# nixie-clock.net
KiCad netlist of a schematic drawn in EAGLE
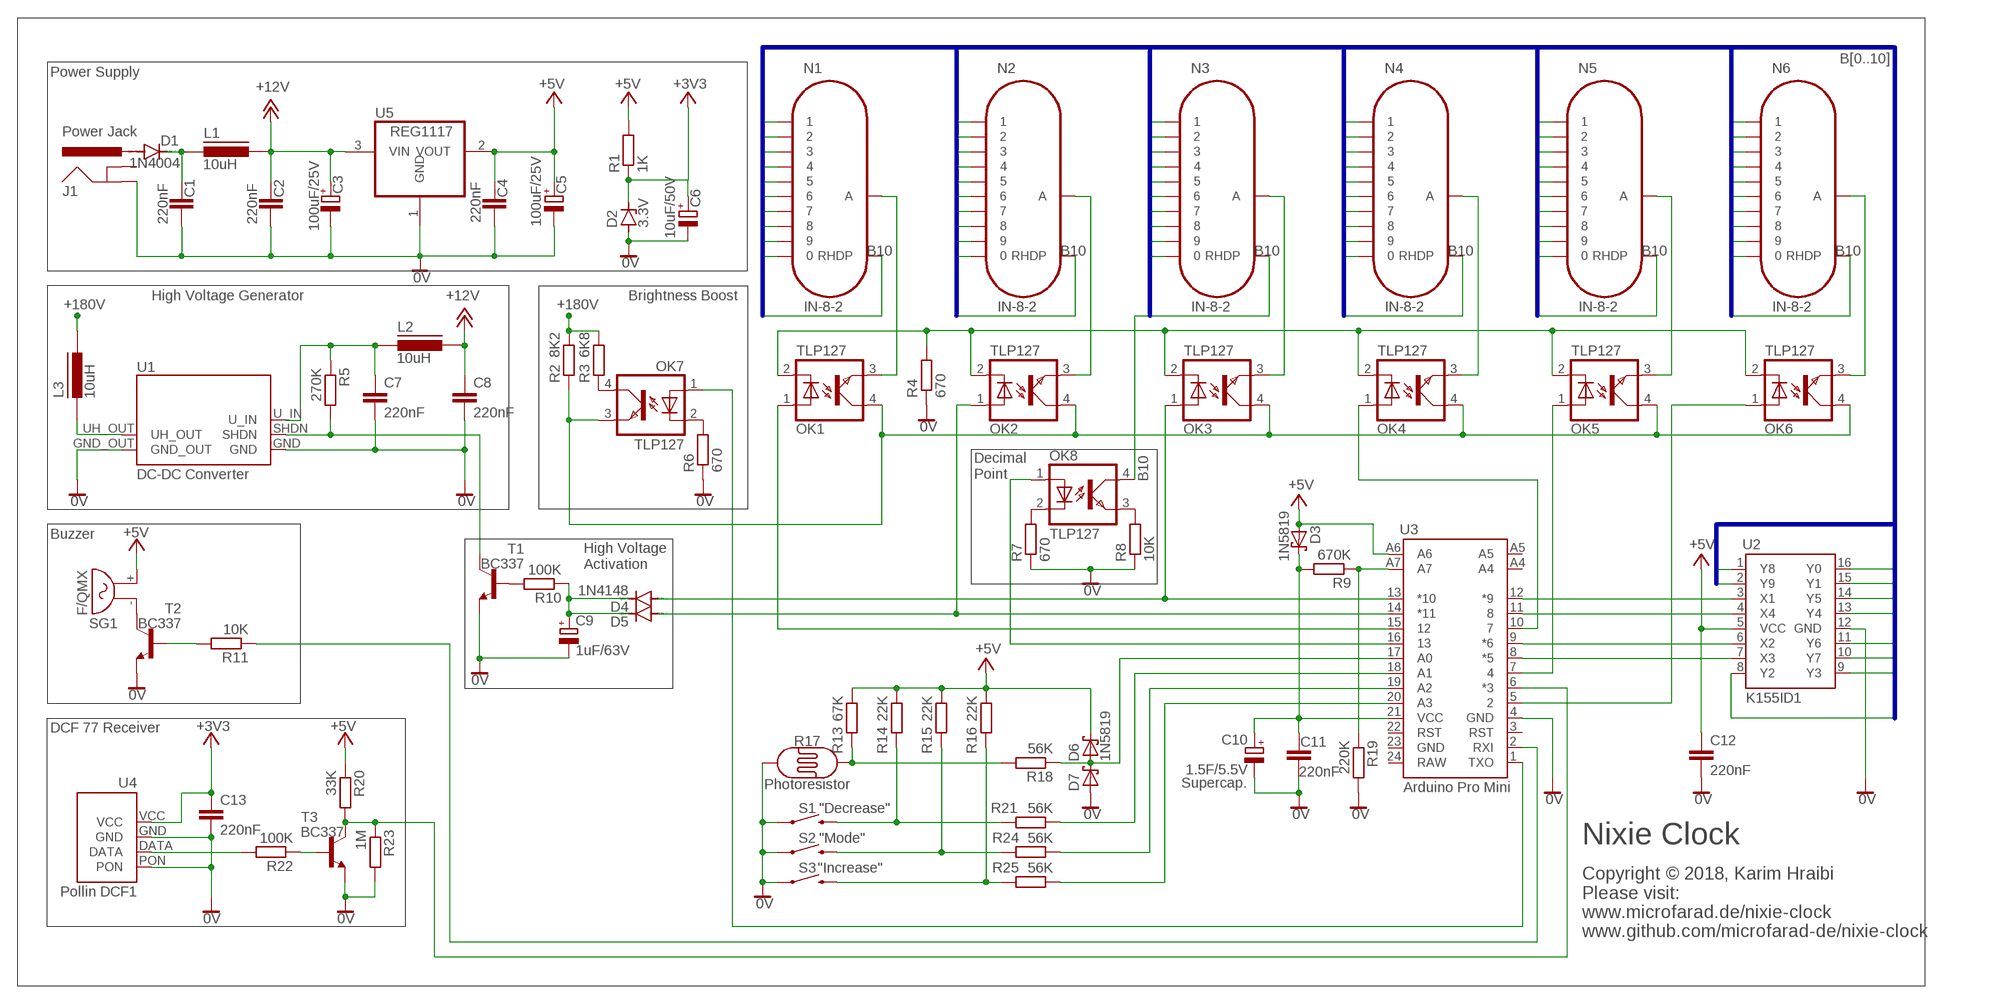
[diagram p0: schematic, sheet 1]

(export (version "E")
  (design (tool "Eeschema 10.0.6"))
  (components
    (comp (ref "C1")
      (value "220nF")
      (footprint "eagle-import:C025-024X044")
      (libsource (lib "eagle-import") (part "C-EU025-024X044"))
    )
    (comp (ref "C2")
      (value "220nF")
      (footprint "eagle-import:C025-024X044")
      (libsource (lib "eagle-import") (part "C-EU025-024X044"))
    )
    (comp (ref "C3")
      (value "100uF/25V")
      (footprint "eagle-import:E2,5-6")
      (libsource (lib "eagle-import") (part "CPOL-EUE2.5-6"))
    )
    (comp (ref "C4")
      (value "220nF")
      (footprint "eagle-import:C025-024X044")
      (libsource (lib "eagle-import") (part "C-EU025-024X044"))
    )
    (comp (ref "C5")
      (value "100uF/25V")
      (footprint "eagle-import:E2,5-6")
      (libsource (lib "eagle-import") (part "CPOL-EUE2.5-6"))
    )
    (comp (ref "C6")
      (value "10uF/50V")
      (footprint "eagle-import:E2-4")
      (libsource (lib "eagle-import") (part "CPOL-EUE2-4"))
    )
    (comp (ref "C7")
      (value "220nF")
      (footprint "eagle-import:C025-024X044")
      (libsource (lib "eagle-import") (part "C-EU025-024X044"))
    )
    (comp (ref "C8")
      (value "220nF")
      (footprint "eagle-import:C025-024X044")
      (libsource (lib "eagle-import") (part "C-EU025-024X044"))
    )
    (comp (ref "C9")
      (value "1uF/63V")
      (footprint "eagle-import:E1,8-4")
      (libsource (lib "eagle-import") (part "CPOL-EUE1.8-4"))
    )
    (comp (ref "C10")
      (value "1.5F/5.5V")
      (footprint "eagle-import:SUPERCAP_1.5F_5.5V")
      (libsource (lib "eagle-import") (part "SUPERCAP/1.5F/5.5V"))
    )
    (comp (ref "C11")
      (value "220nF")
      (footprint "eagle-import:C025-024X044")
      (libsource (lib "eagle-import") (part "C-EU025-024X044"))
    )
    (comp (ref "C12")
      (value "220nF")
      (footprint "eagle-import:C025-024X044")
      (libsource (lib "eagle-import") (part "C-EU025-024X044"))
    )
    (comp (ref "C13")
      (value "220nF")
      (footprint "eagle-import:C025-024X044")
      (libsource (lib "eagle-import") (part "C-EU025-024X044"))
    )
    (comp (ref "D1")
      (value "1N4004")
      (footprint "eagle-import:DO41-10")
      (libsource (lib "eagle-import") (part "1N4004"))
    )
    (comp (ref "D2")
      (value "3.3V")
      (footprint "eagle-import:ZDIO-5")
      (libsource (lib "eagle-import") (part "ZENER-DIODEZD-5"))
    )
    (comp (ref "D3")
      (value "1N5819")
      (footprint "eagle-import:DO41-7.6")
      (libsource (lib "eagle-import") (part "1N5819-B"))
    )
    (comp (ref "D4")
      (value "1N4148")
      (footprint "eagle-import:DO35-7")
      (libsource (lib "eagle-import") (part "1N4148DO35-7"))
    )
    (comp (ref "D5")
      (value "1N4148")
      (footprint "eagle-import:DO35-7")
      (libsource (lib "eagle-import") (part "1N4148DO35-7"))
    )
    (comp (ref "D6")
      (value "1N5819")
      (footprint "eagle-import:DO41-7.6")
      (libsource (lib "eagle-import") (part "1N5819-B"))
    )
    (comp (ref "D7")
      (value "1N5819")
      (footprint "eagle-import:DO41-7.6")
      (libsource (lib "eagle-import") (part "1N5819-B"))
    )
    (comp (ref "J1")
      (value "Power Jack")
      (footprint "eagle-import:POWER_JACK_SLOT")
      (libsource (lib "eagle-import") (part "POWER_JACKSLT"))
    )
    (comp (ref "L1")
      (value "10uH")
      (footprint "eagle-import:CHOKE_9.5MM")
      (libsource (lib "eagle-import") (part "CHOKE/9.5MM"))
    )
    (comp (ref "L2")
      (value "10uH")
      (footprint "eagle-import:CHOKE_9.5MM")
      (libsource (lib "eagle-import") (part "CHOKE/9.5MM"))
    )
    (comp (ref "L3")
      (value "10uH")
      (footprint "eagle-import:CHOKE_9.5MM")
      (libsource (lib "eagle-import") (part "CHOKE/9.5MM"))
    )
    (comp (ref "N1")
      (value "IN-8-2")
      (footprint "eagle-import:IN-8-2")
      (libsource (lib "eagle-import") (part "IN-8-2"))
    )
    (comp (ref "N2")
      (value "IN-8-2")
      (footprint "eagle-import:IN-8-2")
      (libsource (lib "eagle-import") (part "IN-8-2"))
    )
    (comp (ref "N3")
      (value "IN-8-2")
      (footprint "eagle-import:IN-8-2")
      (libsource (lib "eagle-import") (part "IN-8-2"))
    )
    (comp (ref "N4")
      (value "IN-8-2")
      (footprint "eagle-import:IN-8-2")
      (libsource (lib "eagle-import") (part "IN-8-2"))
    )
    (comp (ref "N5")
      (value "IN-8-2")
      (footprint "eagle-import:IN-8-2")
      (libsource (lib "eagle-import") (part "IN-8-2"))
    )
    (comp (ref "N6")
      (value "IN-8-2")
      (footprint "eagle-import:IN-8-2")
      (libsource (lib "eagle-import") (part "IN-8-2"))
    )
    (comp (ref "OK1")
      (value "TLP127")
      (footprint "eagle-import:MINI-FLAT-4")
      (libsource (lib "eagle-import") (part "TLP127"))
    )
    (comp (ref "OK2")
      (value "TLP127")
      (footprint "eagle-import:MINI-FLAT-4")
      (libsource (lib "eagle-import") (part "TLP127"))
    )
    (comp (ref "OK3")
      (value "TLP127")
      (footprint "eagle-import:MINI-FLAT-4")
      (libsource (lib "eagle-import") (part "TLP127"))
    )
    (comp (ref "OK4")
      (value "TLP127")
      (footprint "eagle-import:MINI-FLAT-4")
      (libsource (lib "eagle-import") (part "TLP127"))
    )
    (comp (ref "OK5")
      (value "TLP127")
      (footprint "eagle-import:MINI-FLAT-4")
      (libsource (lib "eagle-import") (part "TLP127"))
    )
    (comp (ref "OK6")
      (value "TLP127")
      (footprint "eagle-import:MINI-FLAT-4")
      (libsource (lib "eagle-import") (part "TLP127"))
    )
    (comp (ref "OK7")
      (value "TLP127")
      (footprint "eagle-import:MINI-FLAT-4")
      (libsource (lib "eagle-import") (part "TLP127"))
    )
    (comp (ref "OK8")
      (value "TLP127")
      (footprint "eagle-import:MINI-FLAT-4")
      (libsource (lib "eagle-import") (part "TLP127"))
    )
    (comp (ref "R1")
      (value "1K")
      (footprint "eagle-import:0207_7")
      (libsource (lib "eagle-import") (part "R-EU_0207/7"))
    )
    (comp (ref "R2")
      (value "8K2")
      (footprint "eagle-import:0207_7")
      (libsource (lib "eagle-import") (part "R-EU_0207/7"))
    )
    (comp (ref "R3")
      (value "6K8")
      (footprint "eagle-import:0207_7")
      (libsource (lib "eagle-import") (part "R-EU_0207/7"))
    )
    (comp (ref "R4")
      (value "670")
      (footprint "eagle-import:0207_7")
      (libsource (lib "eagle-import") (part "R-EU_0207/7"))
    )
    (comp (ref "R5")
      (value "270K")
      (footprint "eagle-import:0207_7")
      (libsource (lib "eagle-import") (part "R-EU_0207/7"))
    )
    (comp (ref "R6")
      (value "670")
      (footprint "eagle-import:0207_7")
      (libsource (lib "eagle-import") (part "R-EU_0207/7"))
    )
    (comp (ref "R7")
      (value "670")
      (footprint "eagle-import:0207_7")
      (libsource (lib "eagle-import") (part "R-EU_0207/7"))
    )
    (comp (ref "R8")
      (value "10K")
      (footprint "eagle-import:0207_7")
      (libsource (lib "eagle-import") (part "R-EU_0207/7"))
    )
    (comp (ref "R9")
      (value "670K")
      (footprint "eagle-import:0207_7")
      (libsource (lib "eagle-import") (part "R-EU_0207/7"))
    )
    (comp (ref "R10")
      (value "100K")
      (footprint "eagle-import:0207_7")
      (libsource (lib "eagle-import") (part "R-EU_0207/7"))
    )
    (comp (ref "R11")
      (value "10K")
      (footprint "eagle-import:0207_7")
      (libsource (lib "eagle-import") (part "R-EU_0207/7"))
    )
    (comp (ref "R13")
      (value "67K")
      (footprint "eagle-import:0207_7")
      (libsource (lib "eagle-import") (part "R-EU_0207/7"))
    )
    (comp (ref "R14")
      (value "22K")
      (footprint "eagle-import:0207_7")
      (libsource (lib "eagle-import") (part "R-EU_0207/7"))
    )
    (comp (ref "R15")
      (value "22K")
      (footprint "eagle-import:0207_7")
      (libsource (lib "eagle-import") (part "R-EU_0207/7"))
    )
    (comp (ref "R16")
      (value "22K")
      (footprint "eagle-import:0207_7")
      (libsource (lib "eagle-import") (part "R-EU_0207/7"))
    )
    (comp (ref "R17")
      (value "Photoresistor")
      (footprint "eagle-import:PHOTOCELL")
      (libsource (lib "eagle-import") (part "PHOTOCELLPTH"))
    )
    (comp (ref "R18")
      (value "56K")
      (footprint "eagle-import:0207_7")
      (libsource (lib "eagle-import") (part "R-EU_0207/7"))
    )
    (comp (ref "R19")
      (value "220K")
      (footprint "eagle-import:0207_7")
      (libsource (lib "eagle-import") (part "R-EU_0207/7"))
    )
    (comp (ref "R20")
      (value "33K")
      (footprint "eagle-import:0207_7")
      (libsource (lib "eagle-import") (part "R-EU_0207/7"))
    )
    (comp (ref "R21")
      (value "56K")
      (footprint "eagle-import:0207_7")
      (libsource (lib "eagle-import") (part "R-EU_0207/7"))
    )
    (comp (ref "R22")
      (value "100K")
      (footprint "eagle-import:0207_7")
      (libsource (lib "eagle-import") (part "R-EU_0207/7"))
    )
    (comp (ref "R23")
      (value "1M")
      (footprint "eagle-import:0207_7")
      (libsource (lib "eagle-import") (part "R-EU_0207/7"))
    )
    (comp (ref "R24")
      (value "56K")
      (footprint "eagle-import:0207_7")
      (libsource (lib "eagle-import") (part "R-EU_0207/7"))
    )
    (comp (ref "R25")
      (value "56K")
      (footprint "eagle-import:0207_7")
      (libsource (lib "eagle-import") (part "R-EU_0207/7"))
    )
    (comp (ref "S1")
      (value "\"Decrease\"")
      (footprint "eagle-import:TACTILE_SWITCH_PTH_6.0MM")
      (libsource (lib "eagle-import") (part "MOMENTARY-SWITCH-SPST-PTH-6.0MM"))
    )
    (comp (ref "S2")
      (value "\"Mode\"")
      (footprint "eagle-import:TACTILE_SWITCH_PTH_6.0MM")
      (libsource (lib "eagle-import") (part "MOMENTARY-SWITCH-SPST-PTH-6.0MM"))
    )
    (comp (ref "S3")
      (value "\"Increase\"")
      (footprint "eagle-import:TACTILE_SWITCH_PTH_6.0MM")
      (libsource (lib "eagle-import") (part "MOMENTARY-SWITCH-SPST-PTH-6.0MM"))
    )
    (comp (ref "SG1")
      (value "F/QMX")
      (footprint "eagle-import:F_QMX")
      (libsource (lib "eagle-import") (part "F/QMX"))
    )
    (comp (ref "T1")
      (value "BC337")
      (footprint "eagle-import:TO92")
      (libsource (lib "eagle-import") (part "BC337"))
    )
    (comp (ref "T2")
      (value "BC337")
      (footprint "eagle-import:TO92")
      (libsource (lib "eagle-import") (part "BC337"))
    )
    (comp (ref "T3")
      (value "BC337")
      (footprint "eagle-import:TO92")
      (libsource (lib "eagle-import") (part "BC337"))
    )
    (comp (ref "U1")
      (value "DC-DC Converter")
      (footprint "eagle-import:CHINA_HV_DC_DC")
      (libsource (lib "eagle-import") (part "CHINA_HV_DC_DC"))
    )
    (comp (ref "U2")
      (value "K155ID1")
      (footprint "eagle-import:DIL16")
      (libsource (lib "eagle-import") (part "K155ID1"))
    )
    (comp (ref "U3")
      (value "Arduino Pro Mini")
      (footprint "eagle-import:ARDUINO_PRO_MINI_TS")
      (libsource (lib "eagle-import") (part "ARDUINO_PRO_MINI_TS"))
    )
    (comp (ref "U4")
      (value "Pollin DCF1")
      (footprint "eagle-import:DCF1")
      (libsource (lib "eagle-import") (part "DCF1"))
    )
    (comp (ref "U5")
      (value "REG1117")
      (footprint "eagle-import:SOT223")
      (libsource (lib "eagle-import") (part "REG1117"))
    )
  )
  (nets
    (net (code "1") (name "+3V3") (class "Default")
      (node (ref "C13") (pin "1") (pinfunction "1_1") (pintype "passive"))
      (node (ref "C6") (pin "+") (pinfunction "+_+") (pintype "passive"))
      (node (ref "D2") (pin "C") (pinfunction "C_C") (pintype "passive"))
      (node (ref "R1") (pin "1") (pinfunction "1_1") (pintype "passive"))
      (node (ref "U4") (pin "VCC") (pinfunction "VCC_VCC") (pintype "power_in"))
    )
    (net (code "2") (name "+5V") (class "Default")
      (node (ref "C12") (pin "1") (pinfunction "1_1") (pintype "passive"))
      (node (ref "C4") (pin "1") (pinfunction "1_1") (pintype "passive"))
      (node (ref "C5") (pin "+") (pinfunction "+_+") (pintype "passive"))
      (node (ref "D3") (pin "A") (pinfunction "A_A") (pintype "passive"))
      (node (ref "D6") (pin "C") (pinfunction "C_C") (pintype "passive"))
      (node (ref "R1") (pin "2") (pinfunction "2_2") (pintype "passive"))
      (node (ref "R13") (pin "1") (pinfunction "1_1") (pintype "passive"))
      (node (ref "R14") (pin "1") (pinfunction "1_1") (pintype "passive"))
      (node (ref "R15") (pin "1") (pinfunction "1_1") (pintype "passive"))
      (node (ref "R16") (pin "1") (pinfunction "1_1") (pintype "passive"))
      (node (ref "R20") (pin "1") (pinfunction "1_1") (pintype "passive"))
      (node (ref "SG1") (pin "+") (pinfunction "2_+") (pintype "passive"))
      (node (ref "U2") (pin "5") (pinfunction "VCC_5") (pintype "power_in"))
      (node (ref "U3") (pin "A6") (pinfunction "A6_A6") (pintype "bidirectional"))
      (node (ref "U5") (pin "2") (pinfunction "VOUT_2") (pintype "output"))
    )
    (net (code "3") (name "+12V") (class "Default")
      (node (ref "C2") (pin "1") (pinfunction "1_1") (pintype "passive"))
      (node (ref "C3") (pin "+") (pinfunction "+_+") (pintype "passive"))
      (node (ref "C8") (pin "1") (pinfunction "1_1") (pintype "passive"))
      (node (ref "L1") (pin "2") (pinfunction "2_2") (pintype "passive"))
      (node (ref "L2") (pin "2") (pinfunction "2_2") (pintype "passive"))
      (node (ref "U5") (pin "3") (pinfunction "VIN_3") (pintype "input"))
    )
    (net (code "4") (name "/+180V") (class "Default")
      (node (ref "L3") (pin "2") (pinfunction "2_2") (pintype "passive"))
      (node (ref "R2") (pin "2") (pinfunction "2_2") (pintype "passive"))
      (node (ref "R3") (pin "2") (pinfunction "2_2") (pintype "passive"))
    )
    (net (code "5") (name "/B0") (class "Default")
      (node (ref "N1") (pin "0") (pinfunction "0_0") (pintype "bidirectional"))
      (node (ref "N2") (pin "0") (pinfunction "0_0") (pintype "bidirectional"))
      (node (ref "N3") (pin "0") (pinfunction "0_0") (pintype "bidirectional"))
      (node (ref "N4") (pin "0") (pinfunction "0_0") (pintype "bidirectional"))
      (node (ref "N5") (pin "0") (pinfunction "0_0") (pintype "bidirectional"))
      (node (ref "N6") (pin "0") (pinfunction "0_0") (pintype "bidirectional"))
      (node (ref "U2") (pin "16") (pinfunction "Y0_16") (pintype "output"))
    )
    (net (code "6") (name "/B1") (class "Default")
      (node (ref "N1") (pin "1") (pinfunction "1_1") (pintype "bidirectional"))
      (node (ref "N2") (pin "1") (pinfunction "1_1") (pintype "bidirectional"))
      (node (ref "N3") (pin "1") (pinfunction "1_1") (pintype "bidirectional"))
      (node (ref "N4") (pin "1") (pinfunction "1_1") (pintype "bidirectional"))
      (node (ref "N5") (pin "1") (pinfunction "1_1") (pintype "bidirectional"))
      (node (ref "N6") (pin "1") (pinfunction "1_1") (pintype "bidirectional"))
      (node (ref "U2") (pin "15") (pinfunction "Y1_15") (pintype "output"))
    )
    (net (code "7") (name "/B2") (class "Default")
      (node (ref "N1") (pin "2") (pinfunction "2_2") (pintype "bidirectional"))
      (node (ref "N2") (pin "2") (pinfunction "2_2") (pintype "bidirectional"))
      (node (ref "N3") (pin "2") (pinfunction "2_2") (pintype "bidirectional"))
      (node (ref "N4") (pin "2") (pinfunction "2_2") (pintype "bidirectional"))
      (node (ref "N5") (pin "2") (pinfunction "2_2") (pintype "bidirectional"))
      (node (ref "N6") (pin "2") (pinfunction "2_2") (pintype "bidirectional"))
      (node (ref "U2") (pin "8") (pinfunction "Y2_8") (pintype "output"))
    )
    (net (code "8") (name "/B3") (class "Default")
      (node (ref "N1") (pin "3") (pinfunction "3_3") (pintype "bidirectional"))
      (node (ref "N2") (pin "3") (pinfunction "3_3") (pintype "bidirectional"))
      (node (ref "N3") (pin "3") (pinfunction "3_3") (pintype "bidirectional"))
      (node (ref "N4") (pin "3") (pinfunction "3_3") (pintype "bidirectional"))
      (node (ref "N5") (pin "3") (pinfunction "3_3") (pintype "bidirectional"))
      (node (ref "N6") (pin "3") (pinfunction "3_3") (pintype "bidirectional"))
      (node (ref "U2") (pin "9") (pinfunction "Y3_9") (pintype "output"))
    )
    (net (code "9") (name "/B4") (class "Default")
      (node (ref "N1") (pin "4") (pinfunction "4_4") (pintype "bidirectional"))
      (node (ref "N2") (pin "4") (pinfunction "4_4") (pintype "bidirectional"))
      (node (ref "N3") (pin "4") (pinfunction "4_4") (pintype "bidirectional"))
      (node (ref "N4") (pin "4") (pinfunction "4_4") (pintype "bidirectional"))
      (node (ref "N5") (pin "4") (pinfunction "4_4") (pintype "bidirectional"))
      (node (ref "N6") (pin "4") (pinfunction "4_4") (pintype "bidirectional"))
      (node (ref "U2") (pin "13") (pinfunction "Y4_13") (pintype "output"))
    )
    (net (code "10") (name "/B5") (class "Default")
      (node (ref "N1") (pin "5") (pinfunction "5_5") (pintype "bidirectional"))
      (node (ref "N2") (pin "5") (pinfunction "5_5") (pintype "bidirectional"))
      (node (ref "N3") (pin "5") (pinfunction "5_5") (pintype "bidirectional"))
      (node (ref "N4") (pin "5") (pinfunction "5_5") (pintype "bidirectional"))
      (node (ref "N5") (pin "5") (pinfunction "5_5") (pintype "bidirectional"))
      (node (ref "N6") (pin "5") (pinfunction "5_5") (pintype "bidirectional"))
      (node (ref "U2") (pin "14") (pinfunction "Y5_14") (pintype "output"))
    )
    (net (code "11") (name "/B6") (class "Default")
      (node (ref "N1") (pin "6") (pinfunction "6_6") (pintype "bidirectional"))
      (node (ref "N2") (pin "6") (pinfunction "6_6") (pintype "bidirectional"))
      (node (ref "N3") (pin "6") (pinfunction "6_6") (pintype "bidirectional"))
      (node (ref "N4") (pin "6") (pinfunction "6_6") (pintype "bidirectional"))
      (node (ref "N5") (pin "6") (pinfunction "6_6") (pintype "bidirectional"))
      (node (ref "N6") (pin "6") (pinfunction "6_6") (pintype "bidirectional"))
      (node (ref "U2") (pin "11") (pinfunction "Y6_11") (pintype "output"))
    )
    (net (code "12") (name "/B7") (class "Default")
      (node (ref "N1") (pin "7") (pinfunction "7_7") (pintype "bidirectional"))
      (node (ref "N2") (pin "7") (pinfunction "7_7") (pintype "bidirectional"))
      (node (ref "N3") (pin "7") (pinfunction "7_7") (pintype "bidirectional"))
      (node (ref "N4") (pin "7") (pinfunction "7_7") (pintype "bidirectional"))
      (node (ref "N5") (pin "7") (pinfunction "7_7") (pintype "bidirectional"))
      (node (ref "N6") (pin "7") (pinfunction "7_7") (pintype "bidirectional"))
      (node (ref "U2") (pin "10") (pinfunction "Y7_10") (pintype "output"))
    )
    (net (code "13") (name "/B8") (class "Default")
      (node (ref "N1") (pin "8") (pinfunction "8_8") (pintype "bidirectional"))
      (node (ref "N2") (pin "8") (pinfunction "8_8") (pintype "bidirectional"))
      (node (ref "N3") (pin "8") (pinfunction "8_8") (pintype "bidirectional"))
      (node (ref "N4") (pin "8") (pinfunction "8_8") (pintype "bidirectional"))
      (node (ref "N5") (pin "8") (pinfunction "8_8") (pintype "bidirectional"))
      (node (ref "N6") (pin "8") (pinfunction "8_8") (pintype "bidirectional"))
      (node (ref "U2") (pin "1") (pinfunction "Y8_1") (pintype "output"))
    )
    (net (code "14") (name "/B9") (class "Default")
      (node (ref "N1") (pin "9") (pinfunction "9_9") (pintype "bidirectional"))
      (node (ref "N2") (pin "9") (pinfunction "9_9") (pintype "bidirectional"))
      (node (ref "N3") (pin "9") (pinfunction "9_9") (pintype "bidirectional"))
      (node (ref "N4") (pin "9") (pinfunction "9_9") (pintype "bidirectional"))
      (node (ref "N5") (pin "9") (pinfunction "9_9") (pintype "bidirectional"))
      (node (ref "N6") (pin "9") (pinfunction "9_9") (pintype "bidirectional"))
      (node (ref "U2") (pin "2") (pinfunction "Y9_2") (pintype "output"))
    )
    (net (code "15") (name "/B10") (class "Default")
      (node (ref "N1") (pin ".") (pinfunction "RHDP_.") (pintype "bidirectional"))
      (node (ref "N2") (pin ".") (pinfunction "RHDP_.") (pintype "bidirectional"))
      (node (ref "N3") (pin ".") (pinfunction "RHDP_.") (pintype "bidirectional"))
      (node (ref "N4") (pin ".") (pinfunction "RHDP_.") (pintype "bidirectional"))
      (node (ref "N5") (pin ".") (pinfunction "RHDP_.") (pintype "bidirectional"))
      (node (ref "N6") (pin ".") (pinfunction "RHDP_.") (pintype "bidirectional"))
      (node (ref "OK8") (pin "4") (pinfunction "COL_4") (pintype "passive"))
    )
    (net (code "17") (name "/GND") (class "Default")
      (node (ref "U3") (pin "23") (pinfunction "GND_23") (pintype "power_in"))
    )
    (net (code "18") (name "/RAW") (class "Default")
      (node (ref "U3") (pin "24") (pinfunction "RAW_24") (pintype "power_in"))
    )
    (net (code "19") (name "0V") (class "Default")
      (node (ref "C1") (pin "2") (pinfunction "2_2") (pintype "passive"))
      (node (ref "C10") (pin "-") (pinfunction "-_-") (pintype "passive"))
      (node (ref "C11") (pin "2") (pinfunction "2_2") (pintype "passive"))
      (node (ref "C12") (pin "2") (pinfunction "2_2") (pintype "passive"))
      (node (ref "C13") (pin "2") (pinfunction "2_2") (pintype "passive"))
      (node (ref "C2") (pin "2") (pinfunction "2_2") (pintype "passive"))
      (node (ref "C3") (pin "-") (pinfunction "-_-") (pintype "passive"))
      (node (ref "C4") (pin "2") (pinfunction "2_2") (pintype "passive"))
      (node (ref "C5") (pin "-") (pinfunction "-_-") (pintype "passive"))
      (node (ref "C6") (pin "-") (pinfunction "-_-") (pintype "passive"))
      (node (ref "C7") (pin "2") (pinfunction "2_2") (pintype "passive"))
      (node (ref "C8") (pin "2") (pinfunction "2_2") (pintype "passive"))
      (node (ref "C9") (pin "-") (pinfunction "-_-") (pintype "passive"))
      (node (ref "D2") (pin "A") (pinfunction "A_A") (pintype "passive"))
      (node (ref "D7") (pin "A") (pinfunction "A_A") (pintype "passive"))
      (node (ref "J1") (pin "GND@2") (pinfunction "GND_GND@2") (pintype "bidirectional"))
      (node (ref "R17") (pin "1") (pinfunction "P$1_1") (pintype "bidirectional"))
      (node (ref "R19") (pin "2") (pinfunction "2_2") (pintype "passive"))
      (node (ref "R23") (pin "2") (pinfunction "2_2") (pintype "passive"))
      (node (ref "R4") (pin "1") (pinfunction "1_1") (pintype "passive"))
      (node (ref "R6") (pin "1") (pinfunction "1_1") (pintype "passive"))
      (node (ref "R7") (pin "1") (pinfunction "1_1") (pintype "passive"))
      (node (ref "R8") (pin "1") (pinfunction "1_1") (pintype "passive"))
      (node (ref "S1") (pin "1") (pinfunction "1_1") (pintype "passive"))
      (node (ref "S2") (pin "1") (pinfunction "1_1") (pintype "passive"))
      (node (ref "S3") (pin "1") (pinfunction "1_1") (pintype "passive"))
      (node (ref "T1") (pin "1") (pinfunction "E_1") (pintype "passive"))
      (node (ref "T2") (pin "1") (pinfunction "E_1") (pintype "passive"))
      (node (ref "T3") (pin "1") (pinfunction "E_1") (pintype "passive"))
      (node (ref "U1") (pin "GND") (pinfunction "GND_GND") (pintype "power_in"))
      (node (ref "U1") (pin "GND_OUT") (pinfunction "GND_OUT_GND_OUT") (pintype "power_in"))
      (node (ref "U2") (pin "12") (pinfunction "GND_12") (pintype "power_in"))
      (node (ref "U3") (pin "4") (pinfunction "GND_4") (pintype "power_in"))
      (node (ref "U4") (pin "GND") (pinfunction "GND_GND") (pintype "power_in"))
      (node (ref "U4") (pin "PON") (pinfunction "PON_PON") (pintype "input"))
      (node (ref "U5") (pin "1") (pinfunction "GND_1") (pintype "power_in"))
    )
    (net (code "20") (name "Net-(C1-Pad1)") (class "Default")
      (node (ref "C1") (pin "1") (pinfunction "1_1") (pintype "passive"))
      (node (ref "D1") (pin "C") (pinfunction "C_C") (pintype "passive"))
      (node (ref "L1") (pin "1") (pinfunction "1_1") (pintype "passive"))
    )
    (net (code "21") (name "Net-(C7-Pad1)") (class "Default")
      (node (ref "C7") (pin "1") (pinfunction "1_1") (pintype "passive"))
      (node (ref "L2") (pin "1") (pinfunction "1_1") (pintype "passive"))
      (node (ref "R5") (pin "1") (pinfunction "1_1") (pintype "passive"))
      (node (ref "U1") (pin "U_IN") (pinfunction "U_IN_U_IN") (pintype "power_in"))
    )
    (net (code "22") (name "Net-(C9-Pad+)") (class "Default")
      (node (ref "C9") (pin "+") (pinfunction "+_+") (pintype "passive"))
      (node (ref "D4") (pin "C") (pinfunction "C_C") (pintype "passive"))
      (node (ref "D5") (pin "C") (pinfunction "C_C") (pintype "passive"))
      (node (ref "R10") (pin "1") (pinfunction "1_1") (pintype "passive"))
    )
    (net (code "23") (name "Net-(D1-PadA)") (class "Default")
      (node (ref "D1") (pin "A") (pinfunction "A_A") (pintype "passive"))
      (node (ref "J1") (pin "PWR") (pinfunction "PWR_PWR") (pintype "bidirectional"))
    )
    (net (code "24") (name "Net-(L3-Pad1)") (class "Default")
      (node (ref "L3") (pin "1") (pinfunction "1_1") (pintype "passive"))
      (node (ref "U1") (pin "UH_OUT") (pinfunction "UH_OUT_UH_OUT") (pintype "output"))
    )
    (net (code "25") (name "Net-(OK1-A)") (class "Default")
      (node (ref "OK1") (pin "1") (pinfunction "A_1") (pintype "passive"))
      (node (ref "U3") (pin "15") (pinfunction "12_15") (pintype "bidirectional"))
    )
    (net (code "26") (name "Net-(OK1-C)") (class "Default")
      (node (ref "OK1") (pin "2") (pinfunction "C_2") (pintype "passive"))
      (node (ref "OK2") (pin "2") (pinfunction "C_2") (pintype "passive"))
      (node (ref "OK3") (pin "2") (pinfunction "C_2") (pintype "passive"))
      (node (ref "OK4") (pin "2") (pinfunction "C_2") (pintype "passive"))
      (node (ref "OK5") (pin "2") (pinfunction "C_2") (pintype "passive"))
      (node (ref "OK6") (pin "2") (pinfunction "C_2") (pintype "passive"))
      (node (ref "R4") (pin "2") (pinfunction "2_2") (pintype "passive"))
    )
    (net (code "27") (name "Net-(OK1-COL)") (class "Default")
      (node (ref "OK1") (pin "4") (pinfunction "COL_4") (pintype "passive"))
      (node (ref "OK2") (pin "4") (pinfunction "COL_4") (pintype "passive"))
      (node (ref "OK3") (pin "4") (pinfunction "COL_4") (pintype "passive"))
      (node (ref "OK4") (pin "4") (pinfunction "COL_4") (pintype "passive"))
      (node (ref "OK5") (pin "4") (pinfunction "COL_4") (pintype "passive"))
      (node (ref "OK6") (pin "4") (pinfunction "COL_4") (pintype "passive"))
      (node (ref "OK7") (pin "3") (pinfunction "EMIT_3") (pintype "passive"))
      (node (ref "R2") (pin "1") (pinfunction "1_1") (pintype "passive"))
    )
    (net (code "28") (name "Net-(OK1-EMIT)") (class "Default")
      (node (ref "N1") (pin "A") (pinfunction "A_A") (pintype "bidirectional"))
      (node (ref "OK1") (pin "3") (pinfunction "EMIT_3") (pintype "passive"))
    )
    (net (code "29") (name "Net-(OK2-A)") (class "Default")
      (node (ref "D5") (pin "A") (pinfunction "A_A") (pintype "passive"))
      (node (ref "OK2") (pin "1") (pinfunction "A_1") (pintype "passive"))
      (node (ref "U3") (pin "14") (pinfunction "*11_14") (pintype "bidirectional"))
    )
    (net (code "30") (name "Net-(OK2-EMIT)") (class "Default")
      (node (ref "N2") (pin "A") (pinfunction "A_A") (pintype "bidirectional"))
      (node (ref "OK2") (pin "3") (pinfunction "EMIT_3") (pintype "passive"))
    )
    (net (code "31") (name "Net-(OK3-A)") (class "Default")
      (node (ref "D4") (pin "A") (pinfunction "A_A") (pintype "passive"))
      (node (ref "OK3") (pin "1") (pinfunction "A_1") (pintype "passive"))
      (node (ref "U3") (pin "13") (pinfunction "*10_13") (pintype "bidirectional"))
    )
    (net (code "32") (name "Net-(OK3-EMIT)") (class "Default")
      (node (ref "N3") (pin "A") (pinfunction "A_A") (pintype "bidirectional"))
      (node (ref "OK3") (pin "3") (pinfunction "EMIT_3") (pintype "passive"))
    )
    (net (code "33") (name "Net-(OK4-A)") (class "Default")
      (node (ref "OK4") (pin "1") (pinfunction "A_1") (pintype "passive"))
      (node (ref "U3") (pin "10") (pinfunction "7_10") (pintype "bidirectional"))
    )
    (net (code "34") (name "Net-(OK4-EMIT)") (class "Default")
      (node (ref "N4") (pin "A") (pinfunction "A_A") (pintype "bidirectional"))
      (node (ref "OK4") (pin "3") (pinfunction "EMIT_3") (pintype "passive"))
    )
    (net (code "35") (name "Net-(OK5-A)") (class "Default")
      (node (ref "OK5") (pin "1") (pinfunction "A_1") (pintype "passive"))
      (node (ref "U3") (pin "7") (pinfunction "4_7") (pintype "bidirectional"))
    )
    (net (code "36") (name "Net-(OK5-EMIT)") (class "Default")
      (node (ref "N5") (pin "A") (pinfunction "A_A") (pintype "bidirectional"))
      (node (ref "OK5") (pin "3") (pinfunction "EMIT_3") (pintype "passive"))
    )
    (net (code "37") (name "Net-(OK6-A)") (class "Default")
      (node (ref "OK6") (pin "1") (pinfunction "A_1") (pintype "passive"))
      (node (ref "U3") (pin "5") (pinfunction "2_5") (pintype "bidirectional"))
    )
    (net (code "38") (name "Net-(OK6-EMIT)") (class "Default")
      (node (ref "N6") (pin "A") (pinfunction "A_A") (pintype "bidirectional"))
      (node (ref "OK6") (pin "3") (pinfunction "EMIT_3") (pintype "passive"))
    )
    (net (code "39") (name "Net-(OK7-A)") (class "Default")
      (node (ref "OK7") (pin "1") (pinfunction "A_1") (pintype "passive"))
      (node (ref "U3") (pin "1") (pinfunction "TXO_1") (pintype "bidirectional"))
    )
    (net (code "40") (name "Net-(OK7-C)") (class "Default")
      (node (ref "OK7") (pin "2") (pinfunction "C_2") (pintype "passive"))
      (node (ref "R6") (pin "2") (pinfunction "2_2") (pintype "passive"))
    )
    (net (code "41") (name "Net-(OK7-COL)") (class "Default")
      (node (ref "OK7") (pin "4") (pinfunction "COL_4") (pintype "passive"))
      (node (ref "R3") (pin "1") (pinfunction "1_1") (pintype "passive"))
    )
    (net (code "42") (name "Net-(OK8-A)") (class "Default")
      (node (ref "OK8") (pin "1") (pinfunction "A_1") (pintype "passive"))
      (node (ref "U3") (pin "16") (pinfunction "13_16") (pintype "bidirectional"))
    )
    (net (code "43") (name "Net-(OK8-C)") (class "Default")
      (node (ref "OK8") (pin "2") (pinfunction "C_2") (pintype "passive"))
      (node (ref "R7") (pin "2") (pinfunction "2_2") (pintype "passive"))
    )
    (net (code "44") (name "Net-(OK8-EMIT)") (class "Default")
      (node (ref "OK8") (pin "3") (pinfunction "EMIT_3") (pintype "passive"))
      (node (ref "R8") (pin "2") (pinfunction "2_2") (pintype "passive"))
    )
    (net (code "45") (name "Net-(R17-P$2)") (class "Default")
      (node (ref "R13") (pin "2") (pinfunction "2_2") (pintype "passive"))
      (node (ref "R17") (pin "2") (pinfunction "P$2_2") (pintype "bidirectional"))
      (node (ref "R18") (pin "2") (pinfunction "2_2") (pintype "passive"))
    )
    (net (code "46") (name "Net-(R19-Pad1)") (class "Default")
      (node (ref "R19") (pin "1") (pinfunction "1_1") (pintype "passive"))
      (node (ref "R9") (pin "1") (pinfunction "1_1") (pintype "passive"))
      (node (ref "U3") (pin "A7") (pinfunction "A7_A7") (pintype "bidirectional"))
    )
    (net (code "47") (name "Net-(R22-Pad2)") (class "Default")
      (node (ref "R22") (pin "2") (pinfunction "2_2") (pintype "passive"))
      (node (ref "U4") (pin "DATA") (pinfunction "DATA_DATA") (pintype "output"))
    )
    (net (code "48") (name "Net-(S1-2)") (class "Default")
      (node (ref "R14") (pin "2") (pinfunction "2_2") (pintype "passive"))
      (node (ref "R21") (pin "2") (pinfunction "2_2") (pintype "passive"))
      (node (ref "S1") (pin "3") (pinfunction "2_3") (pintype "passive"))
    )
    (net (code "49") (name "Net-(S2-2)") (class "Default")
      (node (ref "R15") (pin "2") (pinfunction "2_2") (pintype "passive"))
      (node (ref "R24") (pin "2") (pinfunction "2_2") (pintype "passive"))
      (node (ref "S2") (pin "3") (pinfunction "2_3") (pintype "passive"))
    )
    (net (code "50") (name "Net-(S3-2)") (class "Default")
      (node (ref "R16") (pin "2") (pinfunction "2_2") (pintype "passive"))
      (node (ref "R25") (pin "2") (pinfunction "2_2") (pintype "passive"))
      (node (ref "S3") (pin "3") (pinfunction "2_3") (pintype "passive"))
    )
    (net (code "51") (name "Net-(SG1-1)") (class "Default")
      (node (ref "SG1") (pin "-") (pinfunction "1_-") (pintype "passive"))
      (node (ref "T2") (pin "3") (pinfunction "C_3") (pintype "passive"))
    )
    (net (code "52") (name "Net-(T1-B)") (class "Default")
      (node (ref "R10") (pin "2") (pinfunction "2_2") (pintype "passive"))
      (node (ref "T1") (pin "2") (pinfunction "B_2") (pintype "passive"))
    )
    (net (code "53") (name "Net-(T1-C)") (class "Default")
      (node (ref "R5") (pin "2") (pinfunction "2_2") (pintype "passive"))
      (node (ref "T1") (pin "3") (pinfunction "C_3") (pintype "passive"))
      (node (ref "U1") (pin "SHDN") (pinfunction "SHDN_SHDN") (pintype "input"))
    )
    (net (code "54") (name "Net-(T2-B)") (class "Default")
      (node (ref "R11") (pin "2") (pinfunction "2_2") (pintype "passive"))
      (node (ref "T2") (pin "2") (pinfunction "B_2") (pintype "passive"))
    )
    (net (code "55") (name "Net-(T3-B)") (class "Default")
      (node (ref "R22") (pin "1") (pinfunction "1_1") (pintype "passive"))
      (node (ref "T3") (pin "2") (pinfunction "B_2") (pintype "passive"))
    )
    (net (code "56") (name "Net-(T3-C)") (class "Default")
      (node (ref "R20") (pin "2") (pinfunction "2_2") (pintype "passive"))
      (node (ref "R23") (pin "1") (pinfunction "1_1") (pintype "passive"))
      (node (ref "T3") (pin "3") (pinfunction "C_3") (pintype "passive"))
      (node (ref "U3") (pin "6") (pinfunction "*3_6") (pintype "bidirectional"))
    )
    (net (code "57") (name "Net-(U2-X1)") (class "Default")
      (node (ref "U2") (pin "3") (pinfunction "X1_3") (pintype "input"))
      (node (ref "U3") (pin "12") (pinfunction "*9_12") (pintype "bidirectional"))
    )
    (net (code "58") (name "Net-(U2-X2)") (class "Default")
      (node (ref "U2") (pin "6") (pinfunction "X2_6") (pintype "input"))
      (node (ref "U3") (pin "9") (pinfunction "*6_9") (pintype "bidirectional"))
    )
    (net (code "59") (name "Net-(U2-X3)") (class "Default")
      (node (ref "U2") (pin "7") (pinfunction "X3_7") (pintype "input"))
      (node (ref "U3") (pin "8") (pinfunction "*5_8") (pintype "bidirectional"))
    )
    (net (code "60") (name "Net-(U2-X4)") (class "Default")
      (node (ref "U2") (pin "4") (pinfunction "X4_4") (pintype "input"))
      (node (ref "U3") (pin "11") (pinfunction "8_11") (pintype "bidirectional"))
    )
    (net (code "61") (name "Net-(U3-A0)") (class "Default")
      (node (ref "D6") (pin "A") (pinfunction "A_A") (pintype "passive"))
      (node (ref "D7") (pin "C") (pinfunction "C_C") (pintype "passive"))
      (node (ref "R18") (pin "1") (pinfunction "1_1") (pintype "passive"))
      (node (ref "U3") (pin "17") (pinfunction "A0_17") (pintype "bidirectional"))
    )
    (net (code "62") (name "Net-(U3-A1)") (class "Default")
      (node (ref "R21") (pin "1") (pinfunction "1_1") (pintype "passive"))
      (node (ref "U3") (pin "18") (pinfunction "A1_18") (pintype "bidirectional"))
    )
    (net (code "63") (name "Net-(U3-A2)") (class "Default")
      (node (ref "R24") (pin "1") (pinfunction "1_1") (pintype "passive"))
      (node (ref "U3") (pin "19") (pinfunction "A2_19") (pintype "bidirectional"))
    )
    (net (code "64") (name "Net-(U3-A3)") (class "Default")
      (node (ref "R25") (pin "1") (pinfunction "1_1") (pintype "passive"))
      (node (ref "U3") (pin "20") (pinfunction "A3_20") (pintype "bidirectional"))
    )
    (net (code "65") (name "Net-(U3-RXI)") (class "Default")
      (node (ref "R11") (pin "1") (pinfunction "1_1") (pintype "passive"))
      (node (ref "U3") (pin "2") (pinfunction "RXI_2") (pintype "bidirectional"))
    )
    (net (code "66") (name "Net-(U3-VCC)") (class "Default")
      (node (ref "C10") (pin "+") (pinfunction "+_+") (pintype "passive"))
      (node (ref "C11") (pin "1") (pinfunction "1_1") (pintype "passive"))
      (node (ref "D3") (pin "C") (pinfunction "C_C") (pintype "passive"))
      (node (ref "R9") (pin "2") (pinfunction "2_2") (pintype "passive"))
      (node (ref "U3") (pin "21") (pinfunction "VCC_21") (pintype "power_in"))
    )
    (net (code "67") (name "unconnected-(J1-GNDBREAK-PadGND@1)") (class "Default")
      (node (ref "J1") (pin "GND@1") (pinfunction "GNDBREAK_GND@1") (pintype "bidirectional"))
    )
    (net (code "68") (name "unconnected-(U3-PadA4)") (class "Default")
      (node (ref "U3") (pin "A4") (pinfunction "A4_A4") (pintype "bidirectional"))
    )
    (net (code "69") (name "unconnected-(U3-PadA5)") (class "Default")
      (node (ref "U3") (pin "A5") (pinfunction "A5_A5") (pintype "bidirectional"))
    )
    (net (code "70") (name "unconnected-(U3-RST-Pad3)") (class "Default")
      (node (ref "U3") (pin "3") (pinfunction "RST_3") (pintype "bidirectional"))
    )
    (net (code "71") (name "unconnected-(U3-RST-Pad22)") (class "Default")
      (node (ref "U3") (pin "22") (pinfunction "RST_22") (pintype "bidirectional"))
    )
  )
)
